# Sheet1.net
KiCad netlist of a schematic drawn in Altium Designer
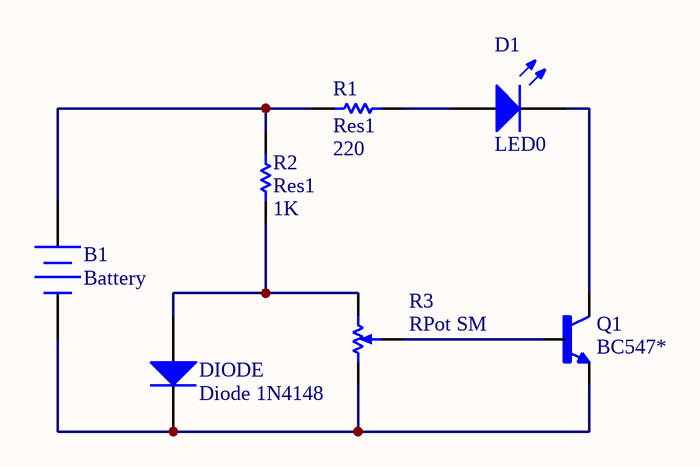
[diagram p0: Sheet1.SchDoc]

(export (version "E")
  (design (tool "Eeschema 10.0.6"))
  (components
    (comp (ref "B1")
      (value "Battery")
      (footprint "BAT-2")
      (description "Multicell Battery")
      (fields (field (name "PUBLISHER") "Altium Limited"))
      (libsource (lib "Miscellaneous Devices") (part "Battery"))
    )
    (comp (ref "D1")
      (value "LED0")
      (footprint "LED-0")
      (description "Typical INFRARED GaAs LED")
      (fields (field (name "PUBLISHER") "Altium Limited"))
      (libsource (lib "Miscellaneous Devices") (part "LED0"))
    )
    (comp (ref "DIODE")
      (value "Diode 1N4148")
      (footprint "DO-35")
      (description "High Conductance Fast Diode")
      (fields (field (name "PUBLISHER") "Altium Limited"))
      (libsource (lib "Miscellaneous Devices") (part "Diode 1N4148"))
    )
    (comp (ref "Q1")
      (value "BC547*")
      (footprint "TO92")
      (description "Trans GP BJT NPN 45V 0.1A 500mW 3-Pin TO-92 T/R")
      (fields (field (name "MF") "ON Semiconductor") (field (name "MP") "BC547"))
      (libsource (lib "BC547") (part "BC547*"))
    )
    (comp (ref "R1")
      (value "Res1")
      (footprint "AXIAL-0.3")
      (description "Resistor")
      (fields (field (name "ALTIUM_VALUE") "220") (field (name "PUBLISHER") "Altium Limited"))
      (libsource (lib "Miscellaneous Devices") (part "Res1"))
    )
    (comp (ref "R2")
      (value "Res1")
      (footprint "AXIAL-0.3")
      (description "Resistor")
      (fields (field (name "ALTIUM_VALUE") "1K") (field (name "PUBLISHER") "Altium Limited"))
      (libsource (lib "Miscellaneous Devices") (part "Res1"))
    )
    (comp (ref "R3")
      (value "RPot SM")
      (footprint "POT4MM-2")
      (description "Square Trimming Potentiometer")
      (fields (field (name "PUBLISHER") "Altium Limited"))
      (libsource (lib "Miscellaneous Devices") (part "RPot SM"))
    )
  )
  (nets
    (net (code "1") (name "Net-(B1-+)") (class "Default")
      (node (ref "B1") (pin "1") (pinfunction "+_1") (pintype "passive"))
      (node (ref "R1") (pin "1") (pinfunction "1_1") (pintype "passive"))
      (node (ref "R2") (pin "2") (pinfunction "2_2") (pintype "passive"))
    )
    (net (code "2") (name "Net-(B1--)") (class "Default")
      (node (ref "B1") (pin "2") (pinfunction "-_2") (pintype "passive"))
      (node (ref "DIODE") (pin "2") (pinfunction "K_2") (pintype "passive"))
      (node (ref "Q1") (pin "1") (pinfunction "E_1") (pintype "passive"))
      (node (ref "R3") (pin "CCW") (pinfunction "-_CCW") (pintype "passive"))
    )
    (net (code "3") (name "Net-(D1-A)") (class "Default")
      (node (ref "D1") (pin "1") (pinfunction "A_1") (pintype "passive"))
      (node (ref "R1") (pin "2") (pinfunction "2_2") (pintype "passive"))
    )
    (net (code "4") (name "Net-(D1-K)") (class "Default")
      (node (ref "D1") (pin "2") (pinfunction "K_2") (pintype "passive"))
      (node (ref "Q1") (pin "3") (pinfunction "C_3") (pintype "passive"))
    )
    (net (code "5") (name "Net-(DIODE-A)") (class "Default")
      (node (ref "DIODE") (pin "1") (pinfunction "A_1") (pintype "passive"))
      (node (ref "R2") (pin "1") (pinfunction "1_1") (pintype "passive"))
      (node (ref "R3") (pin "CW") (pinfunction "+_CW") (pintype "passive"))
    )
    (net (code "6") (name "Net-(Q1-B)") (class "Default")
      (node (ref "Q1") (pin "2") (pinfunction "B_2") (pintype "passive"))
      (node (ref "R3") (pin "W") (pinfunction "W_W") (pintype "passive"))
    )
  )
)
